# Motor.net
KiCad netlist of a schematic drawn in EAGLE
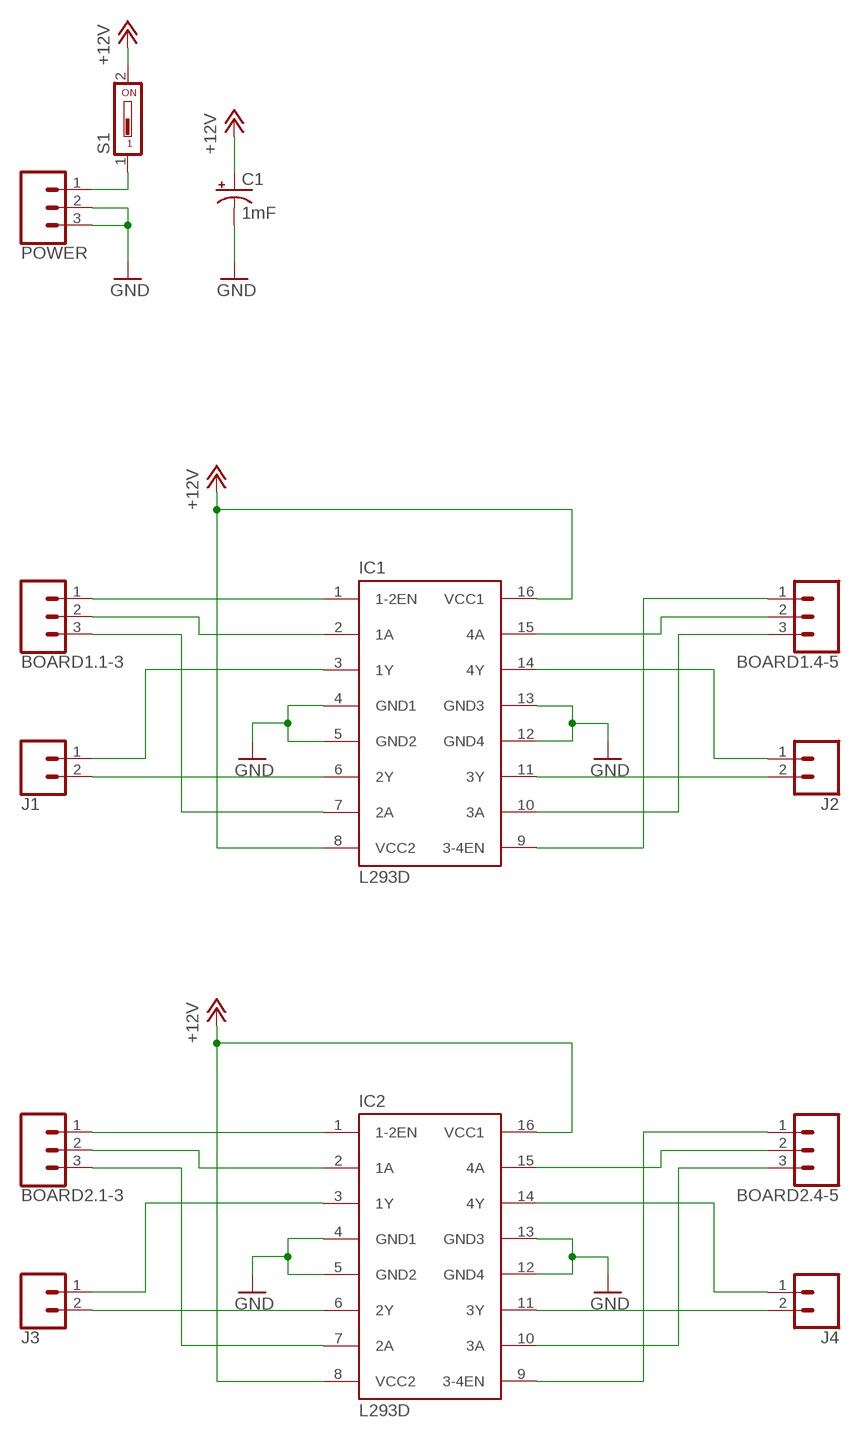
[diagram p0: schematic, sheet 1]

(export (version "E")
  (design (tool "Eeschema 10.0.6"))
  (components
    (comp (ref "BOARD1.1-3")
      (value "CONN_03")
      (footprint "eagle-import:1X03")
      (libsource (lib "eagle-import") (part "CONN_03"))
    )
    (comp (ref "BOARD1.4-5")
      (value "CONN_03")
      (footprint "eagle-import:1X03")
      (libsource (lib "eagle-import") (part "CONN_03"))
    )
    (comp (ref "BOARD2.1-3")
      (value "CONN_03")
      (footprint "eagle-import:1X03")
      (libsource (lib "eagle-import") (part "CONN_03"))
    )
    (comp (ref "BOARD2.4-5")
      (value "CONN_03")
      (footprint "eagle-import:1X03")
      (libsource (lib "eagle-import") (part "CONN_03"))
    )
    (comp (ref "C1")
      (value "1mF")
      (footprint "eagle-import:CPOL-RADIAL-5MM-10MM")
      (libsource (lib "eagle-import") (part "1000UF-RADIAL-5MM-25V-20%"))
    )
    (comp (ref "IC1")
      (value "L293D")
      (footprint "eagle-import:DIL16")
      (libsource (lib "eagle-import") (part "L293D"))
    )
    (comp (ref "IC2")
      (value "L293D")
      (footprint "eagle-import:DIL16")
      (libsource (lib "eagle-import") (part "L293D"))
    )
    (comp (ref "J1")
      (value "CONN_02")
      (footprint "eagle-import:1X02")
      (libsource (lib "eagle-import") (part "CONN_02"))
    )
    (comp (ref "J2")
      (value "CONN_02")
      (footprint "eagle-import:1X02")
      (libsource (lib "eagle-import") (part "CONN_02"))
    )
    (comp (ref "J3")
      (value "CONN_02")
      (footprint "eagle-import:1X02")
      (libsource (lib "eagle-import") (part "CONN_02"))
    )
    (comp (ref "J4")
      (value "CONN_02")
      (footprint "eagle-import:1X02")
      (libsource (lib "eagle-import") (part "CONN_02"))
    )
    (comp (ref "POWER")
      (value "CONN_03")
      (footprint "eagle-import:1X03")
      (libsource (lib "eagle-import") (part "CONN_03"))
    )
    (comp (ref "S1")
      (value "DS01")
      (footprint "eagle-import:DS-01")
      (libsource (lib "eagle-import") (part "DS01"))
    )
  )
  (nets
    (net (code "1") (name "+12V") (class "Default")
      (node (ref "C1") (pin "+") (pinfunction "+_+") (pintype "passive"))
      (node (ref "IC1") (pin "16") (pinfunction "VCC1_16") (pintype "power_in"))
      (node (ref "IC1") (pin "8") (pinfunction "VCC2_8") (pintype "power_in"))
      (node (ref "IC2") (pin "16") (pinfunction "VCC1_16") (pintype "power_in"))
      (node (ref "IC2") (pin "8") (pinfunction "VCC2_8") (pintype "power_in"))
      (node (ref "S1") (pin "2") (pinfunction "2_2") (pintype "passive"))
    )
    (net (code "2") (name "GND") (class "Default")
      (node (ref "C1") (pin "-") (pinfunction "-_-") (pintype "passive"))
      (node (ref "IC1") (pin "12") (pinfunction "GND4_12") (pintype "power_in"))
      (node (ref "IC1") (pin "13") (pinfunction "GND3_13") (pintype "power_in"))
      (node (ref "IC1") (pin "4") (pinfunction "GND1_4") (pintype "power_in"))
      (node (ref "IC1") (pin "5") (pinfunction "GND2_5") (pintype "power_in"))
      (node (ref "IC2") (pin "12") (pinfunction "GND4_12") (pintype "power_in"))
      (node (ref "IC2") (pin "13") (pinfunction "GND3_13") (pintype "power_in"))
      (node (ref "IC2") (pin "4") (pinfunction "GND1_4") (pintype "power_in"))
      (node (ref "IC2") (pin "5") (pinfunction "GND2_5") (pintype "power_in"))
      (node (ref "POWER") (pin "2") (pinfunction "2_2") (pintype "passive"))
      (node (ref "POWER") (pin "3") (pinfunction "3_3") (pintype "passive"))
    )
    (net (code "3") (name "Net-(IC1-1-2EN)") (class "Default")
      (node (ref "BOARD1.1-3") (pin "1") (pinfunction "1_1") (pintype "passive"))
      (node (ref "IC1") (pin "1") (pinfunction "1-2EN_1") (pintype "input"))
    )
    (net (code "4") (name "Net-(IC1-1A)") (class "Default")
      (node (ref "BOARD1.1-3") (pin "2") (pinfunction "2_2") (pintype "passive"))
      (node (ref "IC1") (pin "2") (pinfunction "1A_2") (pintype "input"))
    )
    (net (code "5") (name "Net-(IC1-1Y)") (class "Default")
      (node (ref "IC1") (pin "3") (pinfunction "1Y_3") (pintype "output"))
      (node (ref "J1") (pin "1") (pinfunction "1_1") (pintype "passive"))
    )
    (net (code "6") (name "Net-(IC1-2A)") (class "Default")
      (node (ref "BOARD1.1-3") (pin "3") (pinfunction "3_3") (pintype "passive"))
      (node (ref "IC1") (pin "7") (pinfunction "2A_7") (pintype "input"))
    )
    (net (code "7") (name "Net-(IC1-2Y)") (class "Default")
      (node (ref "IC1") (pin "6") (pinfunction "2Y_6") (pintype "output"))
      (node (ref "J1") (pin "2") (pinfunction "2_2") (pintype "passive"))
    )
    (net (code "8") (name "Net-(IC1-3-4EN)") (class "Default")
      (node (ref "BOARD1.4-5") (pin "1") (pinfunction "1_1") (pintype "passive"))
      (node (ref "IC1") (pin "9") (pinfunction "3-4EN_9") (pintype "input"))
    )
    (net (code "9") (name "Net-(IC1-3A)") (class "Default")
      (node (ref "BOARD1.4-5") (pin "3") (pinfunction "3_3") (pintype "passive"))
      (node (ref "IC1") (pin "10") (pinfunction "3A_10") (pintype "input"))
    )
    (net (code "10") (name "Net-(IC1-3Y)") (class "Default")
      (node (ref "IC1") (pin "11") (pinfunction "3Y_11") (pintype "output"))
      (node (ref "J2") (pin "2") (pinfunction "2_2") (pintype "passive"))
    )
    (net (code "11") (name "Net-(IC1-4A)") (class "Default")
      (node (ref "BOARD1.4-5") (pin "2") (pinfunction "2_2") (pintype "passive"))
      (node (ref "IC1") (pin "15") (pinfunction "4A_15") (pintype "input"))
    )
    (net (code "12") (name "Net-(IC1-4Y)") (class "Default")
      (node (ref "IC1") (pin "14") (pinfunction "4Y_14") (pintype "output"))
      (node (ref "J2") (pin "1") (pinfunction "1_1") (pintype "passive"))
    )
    (net (code "13") (name "Net-(IC2-1-2EN)") (class "Default")
      (node (ref "BOARD2.1-3") (pin "1") (pinfunction "1_1") (pintype "passive"))
      (node (ref "IC2") (pin "1") (pinfunction "1-2EN_1") (pintype "input"))
    )
    (net (code "14") (name "Net-(IC2-1A)") (class "Default")
      (node (ref "BOARD2.1-3") (pin "2") (pinfunction "2_2") (pintype "passive"))
      (node (ref "IC2") (pin "2") (pinfunction "1A_2") (pintype "input"))
    )
    (net (code "15") (name "Net-(IC2-1Y)") (class "Default")
      (node (ref "IC2") (pin "3") (pinfunction "1Y_3") (pintype "output"))
      (node (ref "J3") (pin "1") (pinfunction "1_1") (pintype "passive"))
    )
    (net (code "16") (name "Net-(IC2-2A)") (class "Default")
      (node (ref "BOARD2.1-3") (pin "3") (pinfunction "3_3") (pintype "passive"))
      (node (ref "IC2") (pin "7") (pinfunction "2A_7") (pintype "input"))
    )
    (net (code "17") (name "Net-(IC2-2Y)") (class "Default")
      (node (ref "IC2") (pin "6") (pinfunction "2Y_6") (pintype "output"))
      (node (ref "J3") (pin "2") (pinfunction "2_2") (pintype "passive"))
    )
    (net (code "18") (name "Net-(IC2-3-4EN)") (class "Default")
      (node (ref "BOARD2.4-5") (pin "1") (pinfunction "1_1") (pintype "passive"))
      (node (ref "IC2") (pin "9") (pinfunction "3-4EN_9") (pintype "input"))
    )
    (net (code "19") (name "Net-(IC2-3A)") (class "Default")
      (node (ref "BOARD2.4-5") (pin "3") (pinfunction "3_3") (pintype "passive"))
      (node (ref "IC2") (pin "10") (pinfunction "3A_10") (pintype "input"))
    )
    (net (code "20") (name "Net-(IC2-3Y)") (class "Default")
      (node (ref "IC2") (pin "11") (pinfunction "3Y_11") (pintype "output"))
      (node (ref "J4") (pin "2") (pinfunction "2_2") (pintype "passive"))
    )
    (net (code "21") (name "Net-(IC2-4A)") (class "Default")
      (node (ref "BOARD2.4-5") (pin "2") (pinfunction "2_2") (pintype "passive"))
      (node (ref "IC2") (pin "15") (pinfunction "4A_15") (pintype "input"))
    )
    (net (code "22") (name "Net-(IC2-4Y)") (class "Default")
      (node (ref "IC2") (pin "14") (pinfunction "4Y_14") (pintype "output"))
      (node (ref "J4") (pin "1") (pinfunction "1_1") (pintype "passive"))
    )
    (net (code "23") (name "Net-(POWER-Pad1)") (class "Default")
      (node (ref "POWER") (pin "1") (pinfunction "1_1") (pintype "passive"))
      (node (ref "S1") (pin "1") (pinfunction "1_1") (pintype "passive"))
    )
  )
)
